# eeprom24c32.net
KiCad netlist of a schematic drawn in Altium Designer
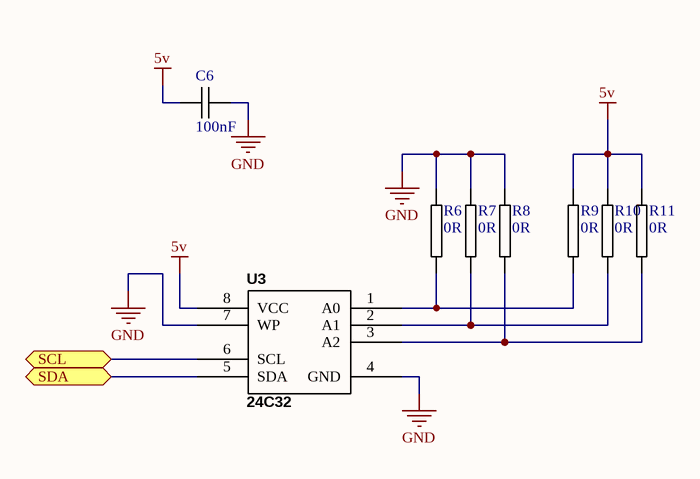
[diagram p0: eeprom24c32.SchDoc]

(export (version "E")
  (design (tool "Eeschema 10.0.6"))
  (components
    (comp (ref "C6")
      (value "100nF")
      (footprint "0805C-TBD")
      (description "CAPACITOR 0805 CERAMIC")
      (libsource (lib "vh_altium_library") (part "0805C-100nF-25V-X7R-MUR"))
    )
    (comp (ref "R6")
      (value "0R")
      (footprint "0805R-GENERIC")
      (description "RESISTOR 0805 1 WATT")
      (libsource (lib "vh_altium_library") (part "0805R-0R"))
    )
    (comp (ref "R7")
      (value "0R")
      (footprint "0805R-GENERIC")
      (description "RESISTOR 0805 1 WATT")
      (libsource (lib "vh_altium_library") (part "0805R-0R"))
    )
    (comp (ref "R8")
      (value "0R")
      (footprint "0805R-GENERIC")
      (description "RESISTOR 0805 1 WATT")
      (libsource (lib "vh_altium_library") (part "0805R-0R"))
    )
    (comp (ref "R9")
      (value "0R")
      (footprint "0805R-GENERIC")
      (description "RESISTOR 0805 1 WATT")
      (libsource (lib "vh_altium_library") (part "0805R-0R"))
    )
    (comp (ref "R10")
      (value "0R")
      (footprint "0805R-GENERIC")
      (description "RESISTOR 0805 1 WATT")
      (libsource (lib "vh_altium_library") (part "0805R-0R"))
    )
    (comp (ref "R11")
      (value "0R")
      (footprint "0805R-GENERIC")
      (description "RESISTOR 0805 1 WATT")
      (libsource (lib "vh_altium_library") (part "0805R-0R"))
    )
    (comp (ref "U3")
      (value "24C32")
      (footprint "SO8")
      (description "IC EEPROM 32KBIT 400KHZ 8SOIC")
      (fields (field (name "MANUFACTURER PART NUMBER") "M24C32-WMN6TP"))
      (libsource (lib "vh_altium_library") (part "24C32"))
    )
  )
  (nets
    (net (code "1") (name "/SCL") (class "Default")
      (node (ref "U3") (pin "6") (pinfunction "SCL_6") (pintype "passive"))
    )
    (net (code "2") (name "/SDA") (class "Default")
      (node (ref "U3") (pin "5") (pinfunction "SDA_5") (pintype "passive"))
    )
    (net (code "3") (name "5v") (class "Default")
      (node (ref "C6") (pin "1") (pintype "passive"))
      (node (ref "R10") (pin "2") (pintype "passive"))
      (node (ref "R11") (pin "2") (pintype "passive"))
      (node (ref "R9") (pin "2") (pintype "passive"))
      (node (ref "U3") (pin "8") (pinfunction "VCC_8") (pintype "passive"))
    )
    (net (code "4") (name "GND") (class "Default")
      (node (ref "C6") (pin "2") (pintype "passive"))
      (node (ref "R6") (pin "2") (pintype "passive"))
      (node (ref "R7") (pin "2") (pintype "passive"))
      (node (ref "R8") (pin "2") (pintype "passive"))
      (node (ref "U3") (pin "4") (pinfunction "GND_4") (pintype "passive"))
      (node (ref "U3") (pin "7") (pinfunction "WP_7") (pintype "passive"))
    )
    (net (code "5") (name "Net-(U3-A0)") (class "Default")
      (node (ref "R6") (pin "1") (pintype "passive"))
      (node (ref "R9") (pin "1") (pintype "passive"))
      (node (ref "U3") (pin "1") (pinfunction "A0_1") (pintype "passive"))
    )
    (net (code "6") (name "Net-(U3-A1)") (class "Default")
      (node (ref "R10") (pin "1") (pintype "passive"))
      (node (ref "R7") (pin "1") (pintype "passive"))
      (node (ref "U3") (pin "2") (pinfunction "A1_2") (pintype "passive"))
    )
    (net (code "7") (name "Net-(U3-A2)") (class "Default")
      (node (ref "R11") (pin "1") (pintype "passive"))
      (node (ref "R8") (pin "1") (pintype "passive"))
      (node (ref "U3") (pin "3") (pinfunction "A2_3") (pintype "passive"))
    )
  )
)
